# Display_Board.net
KiCad netlist of a schematic drawn in EAGLE
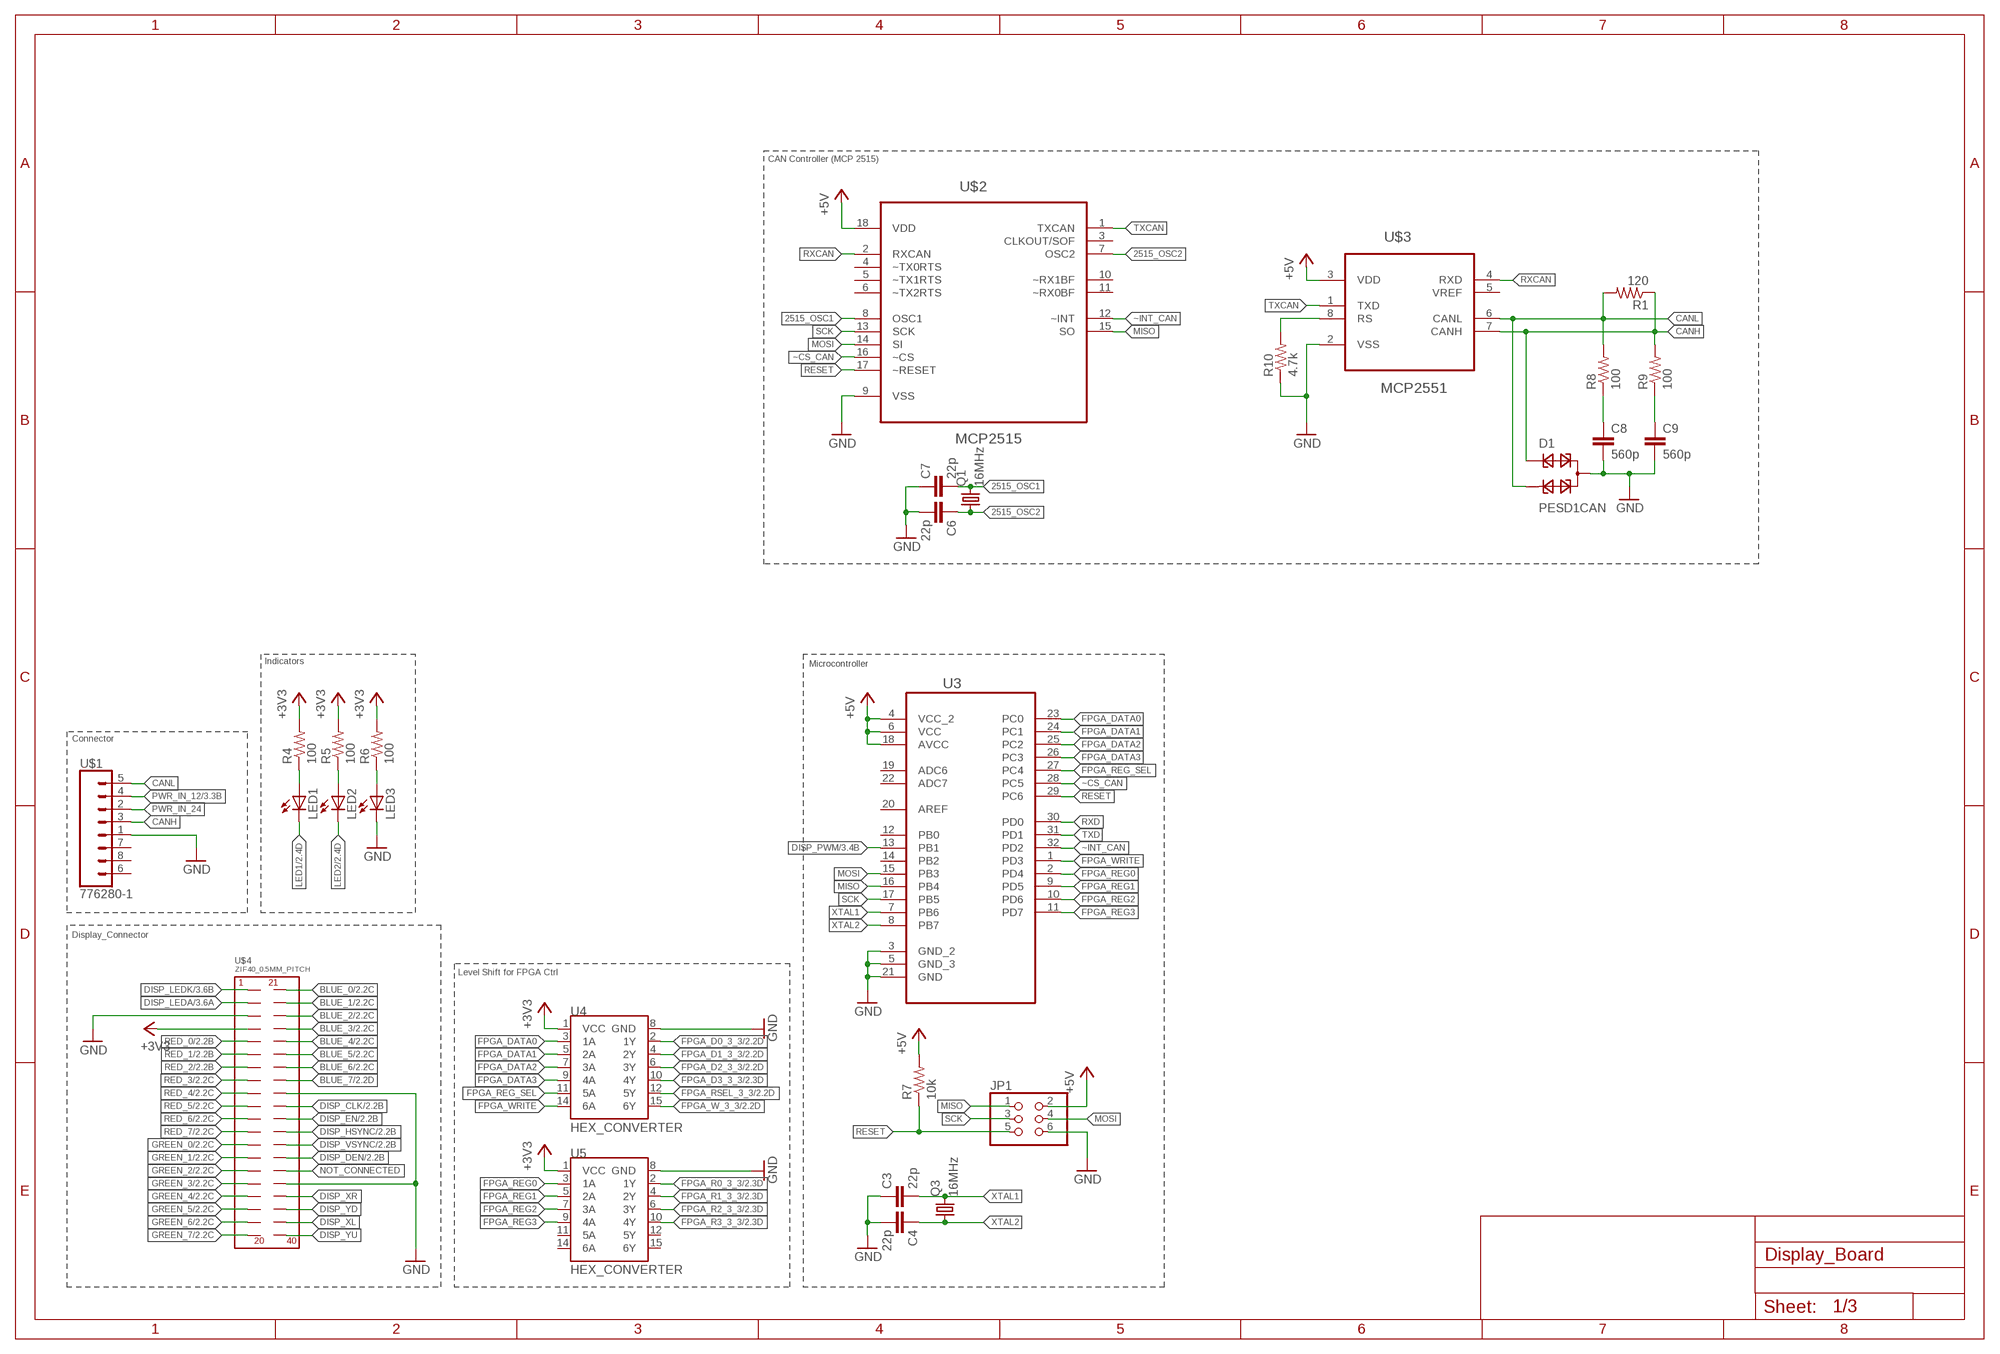
[diagram p0: schematic, sheet 1]
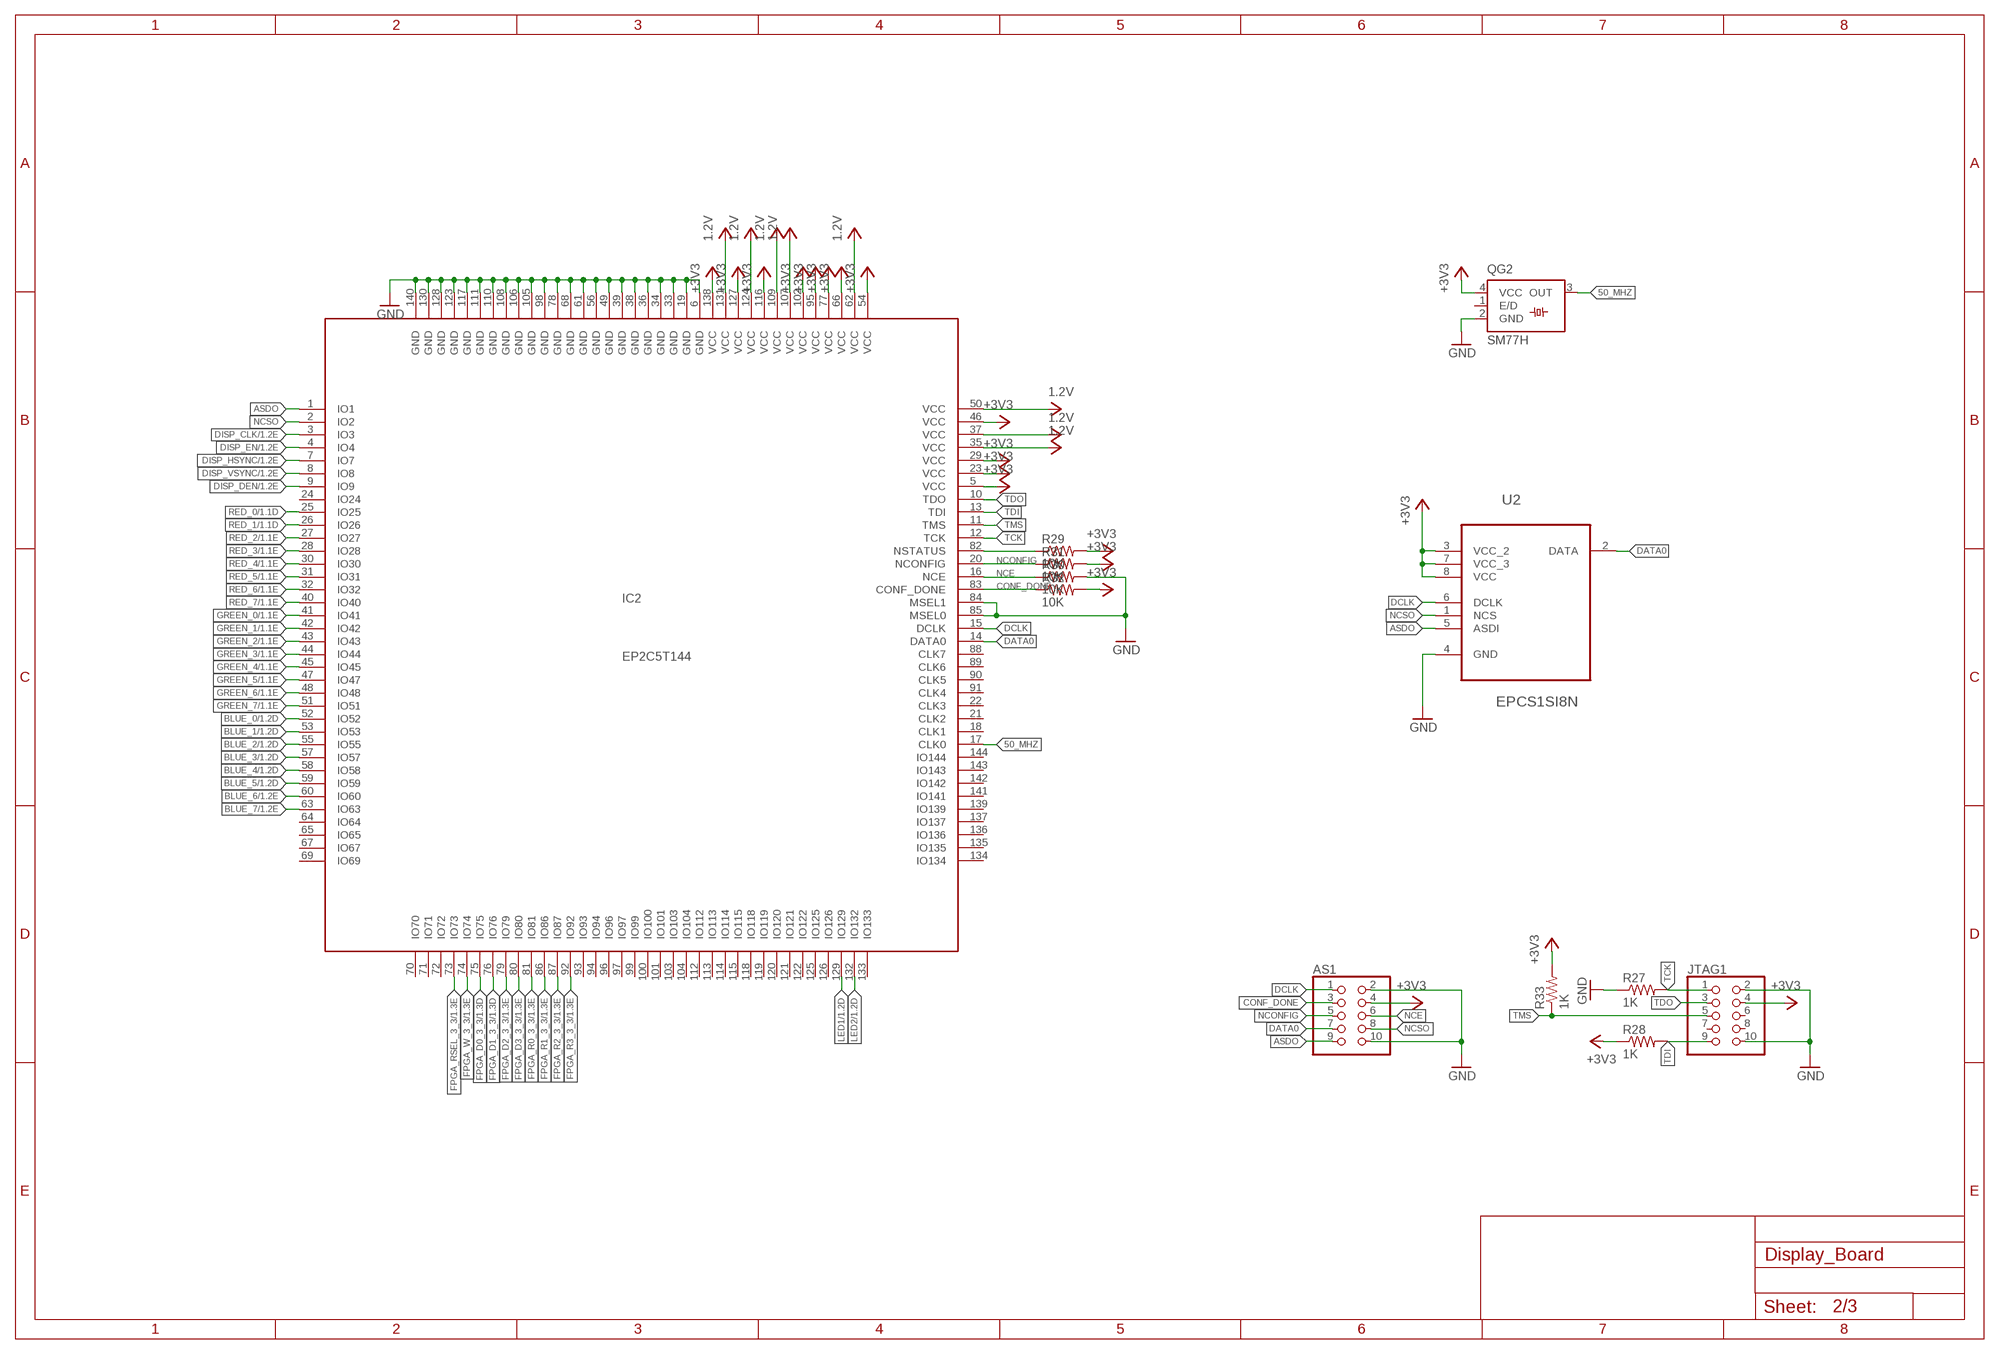
[diagram p1: schematic, sheet 2]
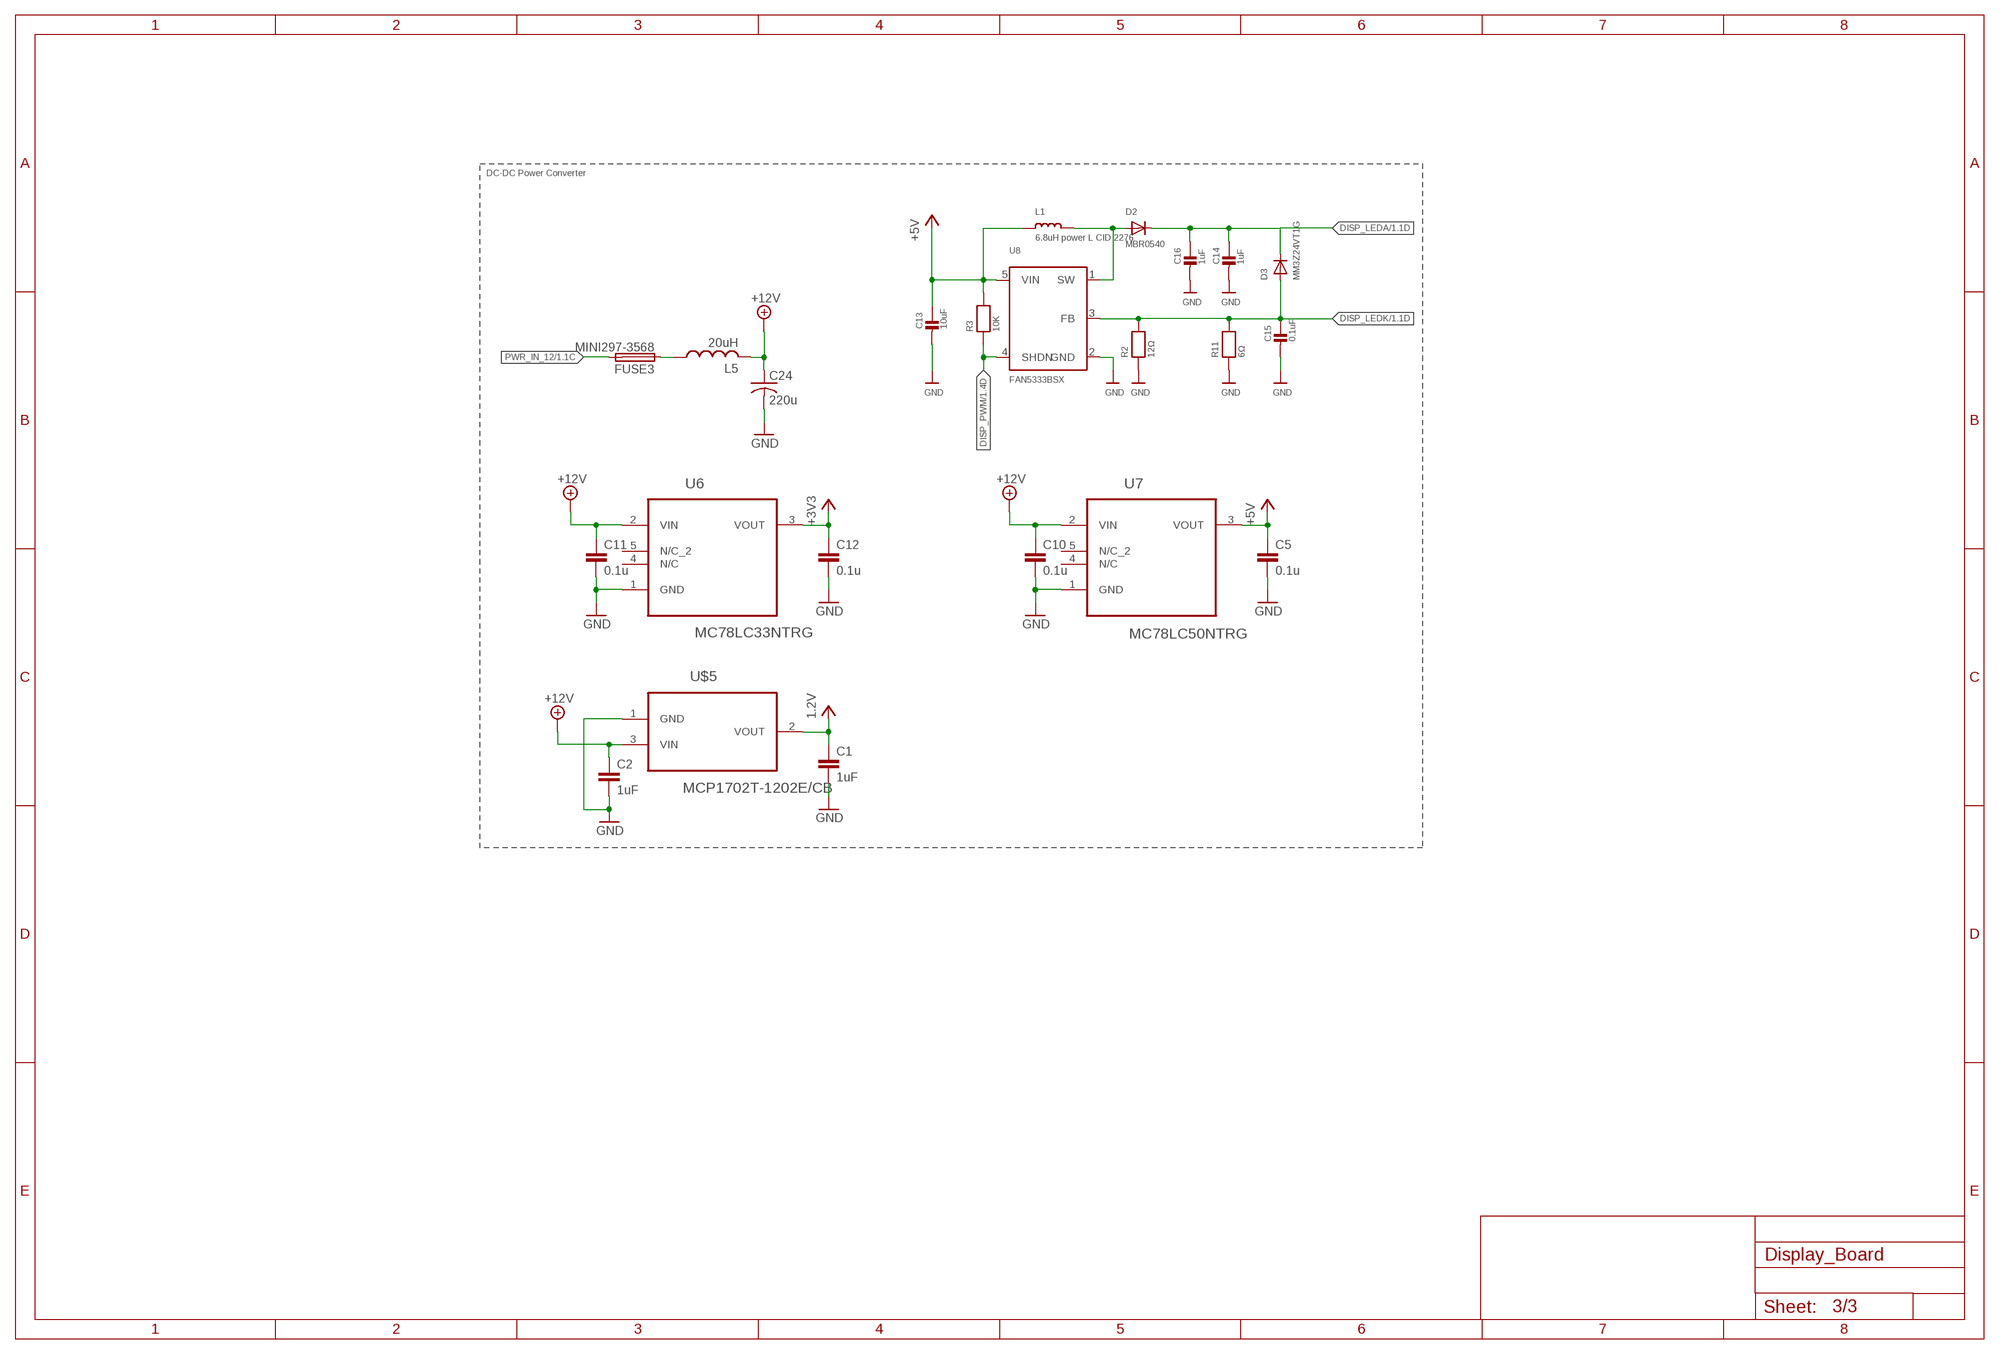
[diagram p2: schematic, sheet 3]

(export (version "E")
  (design (tool "Eeschema 10.0.6"))
  (components
    (comp (ref "AS1")
      (value "PINHD-2X5")
      (footprint "eagle-import:2X05")
      (libsource (lib "eagle-import") (part "PINHD-2X5"))
    )
    (comp (ref "IC2")
      (value "EP2C5T144")
      (footprint "eagle-import:TQFP144")
      (fields (field (name "MPN") "EP2C5T144C8N"))
      (libsource (lib "eagle-import") (part "EP2C5T144"))
    )
    (comp (ref "JTAG1")
      (value "PINHD-2X5")
      (footprint "eagle-import:2X05")
      (libsource (lib "eagle-import") (part "PINHD-2X5"))
    )
    (comp (ref "QG2")
      (value "SM77H")
      (footprint "eagle-import:SM77H")
      (libsource (lib "eagle-import") (part "SM77H"))
    )
    (comp (ref "R27")
      (value "1K")
      (footprint "eagle-import:R0805")
      (libsource (lib "eagle-import") (part "resistor_R-US_R0805"))
    )
    (comp (ref "R28")
      (value "1K")
      (footprint "eagle-import:R0805")
      (libsource (lib "eagle-import") (part "resistor_R-US_R0805"))
    )
    (comp (ref "R29")
      (value "10K")
      (footprint "eagle-import:R0805")
      (libsource (lib "eagle-import") (part "resistor_R-US_R0805"))
    )
    (comp (ref "R30")
      (value "10K")
      (footprint "eagle-import:R0805")
      (libsource (lib "eagle-import") (part "resistor_R-US_R0805"))
    )
    (comp (ref "R31")
      (value "10K")
      (footprint "eagle-import:R0805")
      (libsource (lib "eagle-import") (part "resistor_R-US_R0805"))
    )
    (comp (ref "R32")
      (value "10K")
      (footprint "eagle-import:R0805")
      (libsource (lib "eagle-import") (part "resistor_R-US_R0805"))
    )
    (comp (ref "R33")
      (value "1K")
      (footprint "eagle-import:R0805")
      (libsource (lib "eagle-import") (part "resistor_R-US_R0805"))
    )
    (comp (ref "U2")
      (value "EPCS1SI8N")
      (footprint "eagle-import:SOIC127P600X175-8N")
      (libsource (lib "eagle-import") (part "EPCS1SI8N"))
    )
    (comp (ref "C3")
      (value "22p")
      (footprint "eagle-import:C0805K")
      (libsource (lib "eagle-import") (part "resistor_C-EUC0805K"))
    )
    (comp (ref "C4")
      (value "22p")
      (footprint "eagle-import:C0805K")
      (libsource (lib "eagle-import") (part "resistor_C-EUC0805K"))
    )
    (comp (ref "C6")
      (value "22p")
      (footprint "eagle-import:C0805K")
      (libsource (lib "eagle-import") (part "resistor_C-EUC0805K"))
    )
    (comp (ref "C7")
      (value "22p")
      (footprint "eagle-import:C0805K")
      (libsource (lib "eagle-import") (part "resistor_C-EUC0805K"))
    )
    (comp (ref "C8")
      (value "560p")
      (footprint "eagle-import:C0805K")
      (libsource (lib "eagle-import") (part "C-EUC0805K"))
    )
    (comp (ref "C9")
      (value "560p")
      (footprint "eagle-import:C0805K")
      (libsource (lib "eagle-import") (part "C-EUC0805K"))
    )
    (comp (ref "D1")
      (value "PESD1CAN")
      (footprint "eagle-import:SOT23")
      (libsource (lib "eagle-import") (part "PESD1CAN"))
    )
    (comp (ref "JP1")
      (value "PINHD-2X3")
      (footprint "eagle-import:2X03")
      (libsource (lib "eagle-import") (part "PINHD-2X3"))
    )
    (comp (ref "LED1")
      (value "LEDCHIP-LED0805")
      (footprint "eagle-import:CHIP-LED0805")
      (libsource (lib "eagle-import") (part "LEDCHIP-LED0805"))
    )
    (comp (ref "LED2")
      (value "LEDCHIP-LED0805")
      (footprint "eagle-import:CHIP-LED0805")
      (libsource (lib "eagle-import") (part "LEDCHIP-LED0805"))
    )
    (comp (ref "LED3")
      (value "LEDCHIP-LED0805")
      (footprint "eagle-import:CHIP-LED0805")
      (libsource (lib "eagle-import") (part "LEDCHIP-LED0805"))
    )
    (comp (ref "Q1")
      (value "16MHz")
      (footprint "eagle-import:CTS406")
      (libsource (lib "eagle-import") (part "CRYSTALCTS406"))
    )
    (comp (ref "Q3")
      (value "16MHz")
      (footprint "eagle-import:CTS406")
      (libsource (lib "eagle-import") (part "CRYSTALCTS406"))
    )
    (comp (ref "R1")
      (value "120")
      (footprint "eagle-import:R0805")
      (libsource (lib "eagle-import") (part "R-US_R0805"))
    )
    (comp (ref "R4")
      (value "100")
      (footprint "eagle-import:R0805")
      (libsource (lib "eagle-import") (part "resistor_R-US_R0805"))
    )
    (comp (ref "R5")
      (value "100")
      (footprint "eagle-import:R0805")
      (libsource (lib "eagle-import") (part "resistor_R-US_R0805"))
    )
    (comp (ref "R6")
      (value "100")
      (footprint "eagle-import:R0805")
      (libsource (lib "eagle-import") (part "resistor_R-US_R0805"))
    )
    (comp (ref "R7")
      (value "10k")
      (footprint "eagle-import:R0805")
      (libsource (lib "eagle-import") (part "R-US_R0805"))
    )
    (comp (ref "R8")
      (value "100")
      (footprint "eagle-import:R0805")
      (libsource (lib "eagle-import") (part "R-US_R0805"))
    )
    (comp (ref "R9")
      (value "100")
      (footprint "eagle-import:R0805")
      (libsource (lib "eagle-import") (part "R-US_R0805"))
    )
    (comp (ref "R10")
      (value "4.7k")
      (footprint "eagle-import:R0805")
      (libsource (lib "eagle-import") (part "R-US_R0805"))
    )
    (comp (ref "U$1")
      (value "776280-1")
      (footprint "eagle-import:776280-1")
      (libsource (lib "eagle-import") (part "776280-1"))
    )
    (comp (ref "U$2")
      (value "MCP2515")
      (footprint "eagle-import:SOIC127P1034X264-18N")
      (fields (field (name "MPN") "MCP2515-I/SO"))
      (libsource (lib "eagle-import") (part "MCP2515-I/SO"))
    )
    (comp (ref "U$3")
      (value "MCP2551")
      (footprint "eagle-import:SOIC127P600X175-8N")
      (fields (field (name "MPN") "MCP2551-I/SN"))
      (libsource (lib "eagle-import") (part "MCP2551-I/SN"))
    )
    (comp (ref "U$4")
      (value "ZIF40_0.5MM_PITCH")
      (footprint "eagle-import:ZIF40")
      (libsource (lib "eagle-import") (part "ZIF40_0.5MM_PITCH"))
    )
    (comp (ref "U3")
      (value "ATMEGA328P-AU")
      (footprint "eagle-import:QFP80P900X900X120-32N")
      (libsource (lib "eagle-import") (part "ATMEGA328P-AU"))
    )
    (comp (ref "U4")
      (value "HEX_CONVERTER")
      (footprint "eagle-import:SO016")
      (libsource (lib "eagle-import") (part "HEX_CONVERTER"))
    )
    (comp (ref "U5")
      (value "HEX_CONVERTER")
      (footprint "eagle-import:SO016")
      (libsource (lib "eagle-import") (part "HEX_CONVERTER"))
    )
    (comp (ref "C1")
      (value "1uF")
      (footprint "eagle-import:C0805K")
      (libsource (lib "eagle-import") (part "C-EUC0805K"))
    )
    (comp (ref "C2")
      (value "1uF")
      (footprint "eagle-import:C0805K")
      (libsource (lib "eagle-import") (part "C-EUC0805K"))
    )
    (comp (ref "C5")
      (value "0.1u")
      (footprint "eagle-import:C0805K")
      (libsource (lib "eagle-import") (part "C-EUC0805K"))
    )
    (comp (ref "C10")
      (value "0.1u")
      (footprint "eagle-import:C0805K")
      (libsource (lib "eagle-import") (part "C-EUC0805K"))
    )
    (comp (ref "C11")
      (value "0.1u")
      (footprint "eagle-import:C0805K")
      (libsource (lib "eagle-import") (part "C-EUC0805K"))
    )
    (comp (ref "C12")
      (value "0.1u")
      (footprint "eagle-import:C0805K")
      (libsource (lib "eagle-import") (part "C-EUC0805K"))
    )
    (comp (ref "C13")
      (value "10uF")
      (footprint "eagle-import:_0805MP")
      (libsource (lib "eagle-import") (part "CAP_CERAMIC_0805MP"))
    )
    (comp (ref "C14")
      (value "1uF")
      (footprint "eagle-import:_0805MP")
      (libsource (lib "eagle-import") (part "CAP_CERAMIC_0805MP"))
    )
    (comp (ref "C15")
      (value "0.1uF")
      (footprint "eagle-import:_0805MP")
      (libsource (lib "eagle-import") (part "CAP_CERAMIC_0805MP"))
    )
    (comp (ref "C16")
      (value "1uF")
      (footprint "eagle-import:_0805MP")
      (libsource (lib "eagle-import") (part "CAP_CERAMIC_0805MP"))
    )
    (comp (ref "C24")
      (value "220u")
      (footprint "eagle-import:C1206")
      (libsource (lib "eagle-import") (part "C1206"))
    )
    (comp (ref "D2")
      (value "MBR0540")
      (footprint "eagle-import:SOD-123")
      (libsource (lib "eagle-import") (part "DIODESOD-123"))
    )
    (comp (ref "D3")
      (value "MM3Z24VT1G")
      (footprint "eagle-import:SMADIODE")
      (libsource (lib "eagle-import") (part "DIODESMA"))
    )
    (comp (ref "FUSE3")
      (value "MINI297-3568")
      (footprint "eagle-import:3568")
      (libsource (lib "eagle-import") (part "MINI297-3568"))
    )
    (comp (ref "L1")
      (value "6.8uH power L CID 2276")
      (footprint "eagle-import:INDUCTOR_5X5MM_NR5040_NOTHERMALS")
      (libsource (lib "eagle-import") (part "INDUCTORNR5040"))
    )
    (comp (ref "L5")
      (value "20uH")
      (footprint "eagle-import:MSS7348")
      (libsource (lib "eagle-import") (part "MSS7348"))
    )
    (comp (ref "R2")
      (value "12Ω")
      (footprint "eagle-import:_0805MP")
      (libsource (lib "eagle-import") (part "RESISTOR_0805MP"))
    )
    (comp (ref "R3")
      (value "10K")
      (footprint "eagle-import:_0805MP")
      (libsource (lib "eagle-import") (part "RESISTOR_0805MP"))
    )
    (comp (ref "R11")
      (value "6Ω")
      (footprint "eagle-import:_0805MP")
      (libsource (lib "eagle-import") (part "RESISTOR_0805MP"))
    )
    (comp (ref "U$5")
      (value "MCP1702T-1202E/CB")
      (footprint "eagle-import:SOT95P300X145-3N")
      (fields (field (name "MPN") "MCP1702T-1802E/CB"))
      (libsource (lib "eagle-import") (part "MCP1702T-1802E/CB"))
    )
    (comp (ref "U6")
      (value "MC78LC33NTRG")
      (footprint "eagle-import:SOT95P275X110-5N")
      (libsource (lib "eagle-import") (part "MC78LC33NTRG"))
    )
    (comp (ref "U7")
      (value "MC78LC50NTRG")
      (footprint "eagle-import:SOT95P275X110-5N")
      (libsource (lib "eagle-import") (part "MC78LC50NTRG"))
    )
    (comp (ref "U8")
      (value "FAN5333BSX")
      (footprint "eagle-import:SOT23-5@1")
      (libsource (lib "eagle-import") (part "FAN5331"))
    )
  )
  (nets
    (net (code "1") (name "+3V3") (class "Default")
      (node (ref "AS1") (pin "4") (pinfunction "4_4") (pintype "passive"))
      (node (ref "C12") (pin "1") (pinfunction "1_1") (pintype "passive"))
      (node (ref "IC2") (pin "102") (pinfunction "VCC_102") (pintype "power_in"))
      (node (ref "IC2") (pin "116") (pinfunction "VCC_116") (pintype "power_in"))
      (node (ref "IC2") (pin "127") (pinfunction "VCC_127") (pintype "power_in"))
      (node (ref "IC2") (pin "138") (pinfunction "VCC_138") (pintype "power_in"))
      (node (ref "IC2") (pin "23") (pinfunction "VCC_23") (pintype "power_in"))
      (node (ref "IC2") (pin "29") (pinfunction "VCC_29") (pintype "power_in"))
      (node (ref "IC2") (pin "46") (pinfunction "VCC_46") (pintype "power_in"))
      (node (ref "IC2") (pin "5") (pinfunction "VCC_5") (pintype "power_in"))
      (node (ref "IC2") (pin "54") (pinfunction "VCC_54") (pintype "power_in"))
      (node (ref "IC2") (pin "66") (pinfunction "VCC_66") (pintype "power_in"))
      (node (ref "IC2") (pin "77") (pinfunction "VCC_77") (pintype "power_in"))
      (node (ref "IC2") (pin "95") (pinfunction "VCC_95") (pintype "power_in"))
      (node (ref "JTAG1") (pin "4") (pinfunction "4_4") (pintype "passive"))
      (node (ref "QG2") (pin "4") (pinfunction "VCC_4") (pintype "power_in"))
      (node (ref "R28") (pin "1") (pinfunction "1_1") (pintype "passive"))
      (node (ref "R29") (pin "2") (pinfunction "2_2") (pintype "passive"))
      (node (ref "R31") (pin "2") (pinfunction "2_2") (pintype "passive"))
      (node (ref "R32") (pin "2") (pinfunction "2_2") (pintype "passive"))
      (node (ref "R33") (pin "2") (pinfunction "2_2") (pintype "passive"))
      (node (ref "R4") (pin "2") (pinfunction "2_2") (pintype "passive"))
      (node (ref "R5") (pin "2") (pinfunction "2_2") (pintype "passive"))
      (node (ref "R6") (pin "2") (pinfunction "2_2") (pintype "passive"))
      (node (ref "U$4") (pin "P$4") (pinfunction "P$4_P$4") (pintype "bidirectional"))
      (node (ref "U2") (pin "3") (pinfunction "VCC_2_3") (pintype "power_in"))
      (node (ref "U2") (pin "7") (pinfunction "VCC_3_7") (pintype "power_in"))
      (node (ref "U2") (pin "8") (pinfunction "VCC_8") (pintype "power_in"))
      (node (ref "U4") (pin "1") (pinfunction "VCC_1") (pintype "bidirectional"))
      (node (ref "U5") (pin "1") (pinfunction "VCC_1") (pintype "bidirectional"))
      (node (ref "U6") (pin "3") (pinfunction "VOUT_3") (pintype "output"))
    )
    (net (code "2") (name "+5V") (class "Default")
      (node (ref "C13") (pin "1") (pinfunction "1_1") (pintype "passive"))
      (node (ref "C5") (pin "1") (pinfunction "1_1") (pintype "passive"))
      (node (ref "JP1") (pin "2") (pinfunction "2_2") (pintype "passive"))
      (node (ref "L1") (pin "P$1") (pinfunction "1_P$1") (pintype "passive"))
      (node (ref "R3") (pin "2") (pinfunction "2_2") (pintype "passive"))
      (node (ref "R7") (pin "2") (pinfunction "2_2") (pintype "passive"))
      (node (ref "U$2") (pin "18") (pinfunction "VDD_18") (pintype "power_in"))
      (node (ref "U$3") (pin "3") (pinfunction "VDD_3") (pintype "power_in"))
      (node (ref "U3") (pin "18") (pinfunction "AVCC_18") (pintype "power_in"))
      (node (ref "U3") (pin "4") (pinfunction "VCC_2_4") (pintype "power_in"))
      (node (ref "U3") (pin "6") (pinfunction "VCC_6") (pintype "power_in"))
      (node (ref "U7") (pin "3") (pinfunction "VOUT_3") (pintype "output"))
      (node (ref "U8") (pin "5") (pinfunction "VIN_5") (pintype "bidirectional"))
    )
    (net (code "3") (name "+12V") (class "Default")
      (node (ref "C10") (pin "1") (pinfunction "1_1") (pintype "passive"))
      (node (ref "C11") (pin "1") (pinfunction "1_1") (pintype "passive"))
      (node (ref "C2") (pin "1") (pinfunction "1_1") (pintype "passive"))
      (node (ref "C24") (pin "1") (pinfunction "1_1") (pintype "passive"))
      (node (ref "L5") (pin "P$2") (pinfunction "2_P$2") (pintype "passive"))
      (node (ref "U$5") (pin "3") (pinfunction "VIN_3") (pintype "power_in"))
      (node (ref "U6") (pin "2") (pinfunction "VIN_2") (pintype "power_in"))
      (node (ref "U7") (pin "2") (pinfunction "VIN_2") (pintype "power_in"))
    )
    (net (code "4") (name "50_MHZ") (class "Default")
      (node (ref "IC2") (pin "17") (pinfunction "CLK0_17") (pintype "bidirectional"))
      (node (ref "QG2") (pin "3") (pinfunction "OUT_3") (pintype "output"))
    )
    (net (code "5") (name "2515_OSC1") (class "Default")
      (node (ref "C7") (pin "2") (pinfunction "2_2") (pintype "passive"))
      (node (ref "Q1") (pin "3") (pinfunction "2_3") (pintype "passive"))
      (node (ref "U$2") (pin "8") (pinfunction "OSC1_8") (pintype "input"))
    )
    (net (code "6") (name "2515_OSC2") (class "Default")
      (node (ref "C6") (pin "1") (pinfunction "1_1") (pintype "passive"))
      (node (ref "Q1") (pin "1") (pinfunction "1_1") (pintype "passive"))
      (node (ref "U$2") (pin "7") (pinfunction "OSC2_7") (pintype "output"))
    )
    (net (code "7") (name "ASDO") (class "Default")
      (node (ref "AS1") (pin "9") (pinfunction "9_9") (pintype "passive"))
      (node (ref "IC2") (pin "1") (pinfunction "IO1_1") (pintype "output"))
      (node (ref "U2") (pin "5") (pinfunction "ASDI_5") (pintype "input"))
    )
    (net (code "8") (name "BLUE_0") (class "Default")
      (node (ref "IC2") (pin "52") (pinfunction "IO52_52") (pintype "bidirectional"))
      (node (ref "U$4") (pin "P$21") (pinfunction "P$21_P$21") (pintype "bidirectional"))
    )
    (net (code "9") (name "BLUE_1") (class "Default")
      (node (ref "IC2") (pin "53") (pinfunction "IO53_53") (pintype "bidirectional"))
      (node (ref "U$4") (pin "P$22") (pinfunction "P$22_P$22") (pintype "bidirectional"))
    )
    (net (code "10") (name "BLUE_2") (class "Default")
      (node (ref "IC2") (pin "55") (pinfunction "IO55_55") (pintype "bidirectional"))
      (node (ref "U$4") (pin "P$23") (pinfunction "P$23_P$23") (pintype "bidirectional"))
    )
    (net (code "11") (name "BLUE_3") (class "Default")
      (node (ref "IC2") (pin "57") (pinfunction "IO57_57") (pintype "bidirectional"))
      (node (ref "U$4") (pin "P$24") (pinfunction "P$24_P$24") (pintype "bidirectional"))
    )
    (net (code "12") (name "BLUE_4") (class "Default")
      (node (ref "IC2") (pin "58") (pinfunction "IO58_58") (pintype "bidirectional"))
      (node (ref "U$4") (pin "P$25") (pinfunction "P$25_P$25") (pintype "bidirectional"))
    )
    (net (code "13") (name "BLUE_5") (class "Default")
      (node (ref "IC2") (pin "59") (pinfunction "IO59_59") (pintype "bidirectional"))
      (node (ref "U$4") (pin "P$26") (pinfunction "P$26_P$26") (pintype "bidirectional"))
    )
    (net (code "14") (name "BLUE_6") (class "Default")
      (node (ref "IC2") (pin "60") (pinfunction "IO60_60") (pintype "bidirectional"))
      (node (ref "U$4") (pin "P$27") (pinfunction "P$27_P$27") (pintype "bidirectional"))
    )
    (net (code "15") (name "BLUE_7") (class "Default")
      (node (ref "IC2") (pin "63") (pinfunction "IO63_63") (pintype "bidirectional"))
      (node (ref "U$4") (pin "P$28") (pinfunction "P$28_P$28") (pintype "bidirectional"))
    )
    (net (code "16") (name "CANH") (class "Default")
      (node (ref "D1") (pin "1") (pinfunction "1_1") (pintype "passive"))
      (node (ref "R1") (pin "1") (pinfunction "1_1") (pintype "passive"))
      (node (ref "R9") (pin "2") (pinfunction "2_2") (pintype "passive"))
      (node (ref "U$1") (pin "3") (pinfunction "5_3") (pintype "passive"))
      (node (ref "U$3") (pin "7") (pinfunction "CANH_7") (pintype "bidirectional"))
    )
    (net (code "17") (name "CANL") (class "Default")
      (node (ref "D1") (pin "2") (pinfunction "2_2") (pintype "passive"))
      (node (ref "R1") (pin "2") (pinfunction "2_2") (pintype "passive"))
      (node (ref "R8") (pin "2") (pinfunction "2_2") (pintype "passive"))
      (node (ref "U$1") (pin "5") (pinfunction "8_5") (pintype "passive"))
      (node (ref "U$3") (pin "6") (pinfunction "CANL_6") (pintype "bidirectional"))
    )
    (net (code "18") (name "CONF_DONE") (class "Default")
      (node (ref "AS1") (pin "3") (pinfunction "3_3") (pintype "passive"))
      (node (ref "IC2") (pin "83") (pinfunction "CONF_DONE_83") (pintype "input"))
      (node (ref "R32") (pin "1") (pinfunction "1_1") (pintype "passive"))
    )
    (net (code "19") (name "DATA0") (class "Default")
      (node (ref "AS1") (pin "7") (pinfunction "7_7") (pintype "passive"))
      (node (ref "IC2") (pin "14") (pinfunction "DATA0_14") (pintype "bidirectional"))
      (node (ref "U2") (pin "2") (pinfunction "DATA_2") (pintype "output"))
    )
    (net (code "20") (name "DCLK") (class "Default")
      (node (ref "AS1") (pin "1") (pinfunction "1_1") (pintype "passive"))
      (node (ref "IC2") (pin "15") (pinfunction "DCLK_15") (pintype "bidirectional"))
      (node (ref "U2") (pin "6") (pinfunction "DCLK_6") (pintype "input"))
    )
    (net (code "21") (name "DISP_CLK") (class "Default")
      (node (ref "IC2") (pin "3") (pinfunction "IO3_3") (pintype "bidirectional"))
      (node (ref "U$4") (pin "P$30") (pinfunction "P$30_P$30") (pintype "bidirectional"))
    )
    (net (code "22") (name "DISP_DEN") (class "Default")
      (node (ref "IC2") (pin "9") (pinfunction "IO9_9") (pintype "bidirectional"))
      (node (ref "U$4") (pin "P$34") (pinfunction "P$34_P$34") (pintype "bidirectional"))
    )
    (net (code "23") (name "DISP_EN") (class "Default")
      (node (ref "IC2") (pin "4") (pinfunction "IO4_4") (pintype "bidirectional"))
      (node (ref "U$4") (pin "P$31") (pinfunction "P$31_P$31") (pintype "bidirectional"))
    )
    (net (code "24") (name "DISP_HSYNC") (class "Default")
      (node (ref "IC2") (pin "7") (pinfunction "IO7_7") (pintype "bidirectional"))
      (node (ref "U$4") (pin "P$32") (pinfunction "P$32_P$32") (pintype "bidirectional"))
    )
    (net (code "25") (name "DISP_LEDA") (class "Default")
      (node (ref "C14") (pin "1") (pinfunction "1_1") (pintype "passive"))
      (node (ref "C16") (pin "1") (pinfunction "1_1") (pintype "passive"))
      (node (ref "D2") (pin "C") (pinfunction "C_C") (pintype "passive"))
      (node (ref "D3") (pin "C") (pinfunction "C_C") (pintype "passive"))
      (node (ref "U$4") (pin "P$2") (pinfunction "P$2_P$2") (pintype "bidirectional"))
    )
    (net (code "26") (name "DISP_LEDK") (class "Default")
      (node (ref "C15") (pin "1") (pinfunction "1_1") (pintype "passive"))
      (node (ref "D3") (pin "A") (pinfunction "A_A") (pintype "passive"))
      (node (ref "R11") (pin "2") (pinfunction "2_2") (pintype "passive"))
      (node (ref "R2") (pin "2") (pinfunction "2_2") (pintype "passive"))
      (node (ref "U$4") (pin "P$1") (pinfunction "P$1_P$1") (pintype "bidirectional"))
      (node (ref "U8") (pin "3") (pinfunction "FB_3") (pintype "bidirectional"))
    )
    (net (code "27") (name "DISP_PWM") (class "Default")
      (node (ref "R3") (pin "1") (pinfunction "1_1") (pintype "passive"))
      (node (ref "U3") (pin "13") (pinfunction "PB1_13") (pintype "bidirectional"))
      (node (ref "U8") (pin "4") (pinfunction "SHDN_4") (pintype "bidirectional"))
    )
    (net (code "28") (name "DISP_VSYNC") (class "Default")
      (node (ref "IC2") (pin "8") (pinfunction "IO8_8") (pintype "bidirectional"))
      (node (ref "U$4") (pin "P$33") (pinfunction "P$33_P$33") (pintype "bidirectional"))
    )
    (net (code "29") (name "DISP_XL") (class "Default")
      (node (ref "U$4") (pin "P$39") (pinfunction "P$39_P$39") (pintype "bidirectional"))
    )
    (net (code "30") (name "DISP_XR") (class "Default")
      (node (ref "U$4") (pin "P$37") (pinfunction "P$37_P$37") (pintype "bidirectional"))
    )
    (net (code "31") (name "DISP_YD") (class "Default")
      (node (ref "U$4") (pin "P$38") (pinfunction "P$38_P$38") (pintype "bidirectional"))
    )
    (net (code "32") (name "DISP_YU") (class "Default")
      (node (ref "U$4") (pin "P$40") (pinfunction "P$40_P$40") (pintype "bidirectional"))
    )
    (net (code "33") (name "FPGA_D0_3_3") (class "Default")
      (node (ref "IC2") (pin "75") (pinfunction "IO75_75") (pintype "bidirectional"))
      (node (ref "U4") (pin "2") (pinfunction "1Y_2") (pintype "bidirectional"))
    )
    (net (code "34") (name "FPGA_D1_3_3") (class "Default")
      (node (ref "IC2") (pin "76") (pinfunction "IO76_76") (pintype "bidirectional"))
      (node (ref "U4") (pin "4") (pinfunction "2Y_4") (pintype "bidirectional"))
    )
    (net (code "35") (name "FPGA_D2_3_3") (class "Default")
      (node (ref "IC2") (pin "79") (pinfunction "IO79_79") (pintype "bidirectional"))
      (node (ref "U4") (pin "6") (pinfunction "3Y_6") (pintype "bidirectional"))
    )
    (net (code "36") (name "FPGA_D3_3_3") (class "Default")
      (node (ref "IC2") (pin "80") (pinfunction "IO80_80") (pintype "bidirectional"))
      (node (ref "U4") (pin "10") (pinfunction "4Y_10") (pintype "bidirectional"))
    )
    (net (code "37") (name "FPGA_DATA0") (class "Default")
      (node (ref "U3") (pin "23") (pinfunction "PC0_23") (pintype "bidirectional"))
      (node (ref "U4") (pin "3") (pinfunction "1A_3") (pintype "bidirectional"))
    )
    (net (code "38") (name "FPGA_DATA1") (class "Default")
      (node (ref "U3") (pin "24") (pinfunction "PC1_24") (pintype "bidirectional"))
      (node (ref "U4") (pin "5") (pinfunction "2A_5") (pintype "bidirectional"))
    )
    (net (code "39") (name "FPGA_DATA2") (class "Default")
      (node (ref "U3") (pin "25") (pinfunction "PC2_25") (pintype "bidirectional"))
      (node (ref "U4") (pin "7") (pinfunction "3A_7") (pintype "bidirectional"))
    )
    (net (code "40") (name "FPGA_DATA3") (class "Default")
      (node (ref "U3") (pin "26") (pinfunction "PC3_26") (pintype "bidirectional"))
      (node (ref "U4") (pin "9") (pinfunction "4A_9") (pintype "bidirectional"))
    )
    (net (code "41") (name "FPGA_R0_3_3") (class "Default")
      (node (ref "IC2") (pin "81") (pinfunction "IO81_81") (pintype "bidirectional"))
      (node (ref "U5") (pin "2") (pinfunction "1Y_2") (pintype "bidirectional"))
    )
    (net (code "42") (name "FPGA_R1_3_3") (class "Default")
      (node (ref "IC2") (pin "86") (pinfunction "IO86_86") (pintype "bidirectional"))
      (node (ref "U5") (pin "4") (pinfunction "2Y_4") (pintype "bidirectional"))
    )
    (net (code "43") (name "FPGA_R2_3_3") (class "Default")
      (node (ref "IC2") (pin "87") (pinfunction "IO87_87") (pintype "bidirectional"))
      (node (ref "U5") (pin "6") (pinfunction "3Y_6") (pintype "bidirectional"))
    )
    (net (code "44") (name "FPGA_R3_3_3") (class "Default")
      (node (ref "IC2") (pin "92") (pinfunction "IO92_92") (pintype "bidirectional"))
      (node (ref "U5") (pin "10") (pinfunction "4Y_10") (pintype "bidirectional"))
    )
    (net (code "45") (name "FPGA_REG0") (class "Default")
      (node (ref "U3") (pin "2") (pinfunction "PD4_2") (pintype "bidirectional"))
      (node (ref "U5") (pin "3") (pinfunction "1A_3") (pintype "bidirectional"))
    )
    (net (code "46") (name "FPGA_REG1") (class "Default")
      (node (ref "U3") (pin "9") (pinfunction "PD5_9") (pintype "bidirectional"))
      (node (ref "U5") (pin "5") (pinfunction "2A_5") (pintype "bidirectional"))
    )
    (net (code "47") (name "FPGA_REG2") (class "Default")
      (node (ref "U3") (pin "10") (pinfunction "PD6_10") (pintype "bidirectional"))
      (node (ref "U5") (pin "7") (pinfunction "3A_7") (pintype "bidirectional"))
    )
    (net (code "48") (name "FPGA_REG3") (class "Default")
      (node (ref "U3") (pin "11") (pinfunction "PD7_11") (pintype "bidirectional"))
      (node (ref "U5") (pin "9") (pinfunction "4A_9") (pintype "bidirectional"))
    )
    (net (code "49") (name "FPGA_REG_SEL") (class "Default")
      (node (ref "U3") (pin "27") (pinfunction "PC4_27") (pintype "bidirectional"))
      (node (ref "U4") (pin "11") (pinfunction "5A_11") (pintype "bidirectional"))
    )
    (net (code "50") (name "FPGA_RSEL_3_3") (class "Default")
      (node (ref "IC2") (pin "73") (pinfunction "IO73_73") (pintype "bidirectional"))
      (node (ref "U4") (pin "12") (pinfunction "5Y_12") (pintype "bidirectional"))
    )
    (net (code "51") (name "FPGA_WRITE") (class "Default")
      (node (ref "U3") (pin "1") (pinfunction "PD3_1") (pintype "bidirectional"))
      (node (ref "U4") (pin "14") (pinfunction "6A_14") (pintype "bidirectional"))
    )
    (net (code "52") (name "FPGA_W_3_3") (class "Default")
      (node (ref "IC2") (pin "74") (pinfunction "IO74_74") (pintype "bidirectional"))
      (node (ref "U4") (pin "15") (pinfunction "6Y_15") (pintype "bidirectional"))
    )
    (net (code "53") (name "GND") (class "Default")
      (node (ref "AS1") (pin "10") (pinfunction "10_10") (pintype "passive"))
      (node (ref "AS1") (pin "2") (pinfunction "2_2") (pintype "passive"))
      (node (ref "C1") (pin "2") (pinfunction "2_2") (pintype "passive"))
      (node (ref "C10") (pin "2") (pinfunction "2_2") (pintype "passive"))
      (node (ref "C11") (pin "2") (pinfunction "2_2") (pintype "passive"))
      (node (ref "C12") (pin "2") (pinfunction "2_2") (pintype "passive"))
      (node (ref "C13") (pin "2") (pinfunction "2_2") (pintype "passive"))
      (node (ref "C14") (pin "2") (pinfunction "2_2") (pintype "passive"))
      (node (ref "C15") (pin "2") (pinfunction "2_2") (pintype "passive"))
      (node (ref "C16") (pin "2") (pinfunction "2_2") (pintype "passive"))
      (node (ref "C2") (pin "2") (pinfunction "2_2") (pintype "passive"))
      (node (ref "C24") (pin "2") (pinfunction "2_2") (pintype "passive"))
      (node (ref "C3") (pin "1") (pinfunction "1_1") (pintype "passive"))
      (node (ref "C4") (pin "2") (pinfunction "2_2") (pintype "passive"))
      (node (ref "C5") (pin "2") (pinfunction "2_2") (pintype "passive"))
      (node (ref "C6") (pin "2") (pinfunction "2_2") (pintype "passive"))
      (node (ref "C7") (pin "1") (pinfunction "1_1") (pintype "passive"))
      (node (ref "C8") (pin "2") (pinfunction "2_2") (pintype "passive"))
      (node (ref "C9") (pin "2") (pinfunction "2_2") (pintype "passive"))
      (node (ref "D1") (pin "3") (pinfunction "3_3") (pintype "passive"))
      (node (ref "IC2") (pin "105") (pinfunction "GND_105") (pintype "power_in"))
      (node (ref "IC2") (pin "106") (pinfunction "GND_106") (pintype "power_in"))
      (node (ref "IC2") (pin "108") (pinfunction "GND_108") (pintype "power_in"))
      (node (ref "IC2") (pin "110") (pinfunction "GND_110") (pintype "power_in"))
      (node (ref "IC2") (pin "111") (pinfunction "GND_111") (pintype "power_in"))
      (node (ref "IC2") (pin "117") (pinfunction "GND_117") (pintype "power_in"))
      (node (ref "IC2") (pin "123") (pinfunction "GND_123") (pintype "power_in"))
      (node (ref "IC2") (pin "128") (pinfunction "GND_128") (pintype "power_in"))
      (node (ref "IC2") (pin "130") (pinfunction "GND_130") (pintype "power_in"))
      (node (ref "IC2") (pin "140") (pinfunction "GND_140") (pintype "power_in"))
      (node (ref "IC2") (pin "19") (pinfunction "GND_19") (pintype "power_in"))
      (node (ref "IC2") (pin "33") (pinfunction "GND_33") (pintype "power_in"))
      (node (ref "IC2") (pin "34") (pinfunction "GND_34") (pintype "power_in"))
      (node (ref "IC2") (pin "36") (pinfunction "GND_36") (pintype "power_in"))
      (node (ref "IC2") (pin "38") (pinfunction "GND_38") (pintype "power_in"))
      (node (ref "IC2") (pin "39") (pinfunction "GND_39") (pintype "power_in"))
      (node (ref "IC2") (pin "49") (pinfunction "GND_49") (pintype "power_in"))
      (node (ref "IC2") (pin "56") (pinfunction "GND_56") (pintype "power_in"))
      (node (ref "IC2") (pin "6") (pinfunction "GND_6") (pintype "power_in"))
      (node (ref "IC2") (pin "61") (pinfunction "GND_61") (pintype "power_in"))
      (node (ref "IC2") (pin "68") (pinfunction "GND_68") (pintype "power_in"))
      (node (ref "IC2") (pin "78") (pinfunction "GND_78") (pintype "power_in"))
      (node (ref "IC2") (pin "84") (pinfunction "MSEL1_84") (pintype "input"))
      (node (ref "IC2") (pin "85") (pinfunction "MSEL0_85") (pintype "input"))
      (node (ref "IC2") (pin "98") (pinfunction "GND_98") (pintype "power_in"))
      (node (ref "JP1") (pin "6") (pinfunction "6_6") (pintype "passive"))
      (node (ref "JTAG1") (pin "10") (pinfunction "10_10") (pintype "passive"))
      (node (ref "JTAG1") (pin "2") (pinfunction "2_2") (pintype "passive"))
      (node (ref "LED3") (pin "C") (pinfunction "C_C") (pintype "passive"))
      (node (ref "QG2") (pin "2") (pinfunction "GND_2") (pintype "power_in"))
      (node (ref "R10") (pin "1") (pinfunction "1_1") (pintype "passive"))
      (node (ref "R11") (pin "1") (pinfunction "1_1") (pintype "passive"))
      (node (ref "R2") (pin "1") (pinfunction "1_1") (pintype "passive"))
      (node (ref "R27") (pin "1") (pinfunction "1_1") (pintype "passive"))
      (node (ref "R30") (pin "2") (pinfunction "2_2") (pintype "passive"))
      (node (ref "U$1") (pin "1") (pinfunction "4_1") (pintype "passive"))
      (node (ref "U$2") (pin "9") (pinfunction "VSS_9") (pintype "power_in"))
      (node (ref "U$3") (pin "2") (pinfunction "VSS_2") (pintype "passive"))
      (node (ref "U$4") (pin "P$29") (pinfunction "P$29_P$29") (pintype "bidirectional"))
      (node (ref "U$4") (pin "P$3") (pinfunction "P$3_P$3") (pintype "bidirectional"))
      (node (ref "U$4") (pin "P$36") (pinfunction "P$36_P$36") (pintype "bidirectional"))
      (node (ref "U$5") (pin "1") (pinfunction "GND_1") (pintype "passive"))
      (node (ref "U2") (pin "4") (pinfunction "GND_4") (pintype "passive"))
      (node (ref "U3") (pin "21") (pinfunction "GND_21") (pintype "passive"))
      (node (ref "U3") (pin "3") (pinfunction "GND_2_3") (pintype "passive"))
      (node (ref "U3") (pin "5") (pinfunction "GND_3_5") (pintype "passive"))
      (node (ref "U4") (pin "8") (pinfunction "GND_8") (pintype "bidirectional"))
      (node (ref "U5") (pin "8") (pinfunction "GND_8") (pintype "bidirectional"))
      (node (ref "U6") (pin "1") (pinfunction "GND_1") (pintype "passive"))
      (node (ref "U7") (pin "1") (pinfunction "GND_1") (pintype "passive"))
      (node (ref "U8") (pin "2") (pinfunction "GND_2") (pintype "bidirectional"))
    )
    (net (code "54") (name "GREEN_0") (class "Default")
      (node (ref "IC2") (pin "41") (pinfunction "IO41_41") (pintype "bidirectional"))
      (node (ref "U$4") (pin "P$13") (pinfunction "P$13_P$13") (pintype "bidirectional"))
    )
    (net (code "55") (name "GREEN_1") (class "Default")
      (node (ref "IC2") (pin "42") (pinfunction "IO42_42") (pintype "bidirectional"))
      (node (ref "U$4") (pin "P$14") (pinfunction "P$14_P$14") (pintype "bidirectional"))
    )
    (net (code "56") (name "GREEN_2") (class "Default")
      (node (ref "IC2") (pin "43") (pinfunction "IO43_43") (pintype "bidirectional"))
      (node (ref "U$4") (pin "P$15") (pinfunction "P$15_P$15") (pintype "bidirectional"))
    )
    (net (code "57") (name "GREEN_3") (class "Default")
      (node (ref "IC2") (pin "44") (pinfunction "IO44_44") (pintype "bidirectional"))
      (node (ref "U$4") (pin "P$16") (pinfunction "P$16_P$16") (pintype "bidirectional"))
    )
    (net (code "58") (name "GREEN_4") (class "Default")
      (node (ref "IC2") (pin "45") (pinfunction "IO45_45") (pintype "bidirectional"))
      (node (ref "U$4") (pin "P$17") (pinfunction "P$17_P$17") (pintype "bidirectional"))
    )
    (net (code "59") (name "GREEN_5") (class "Default")
      (node (ref "IC2") (pin "47") (pinfunction "IO47_47") (pintype "bidirectional"))
      (node (ref "U$4") (pin "P$18") (pinfunction "P$18_P$18") (pintype "bidirectional"))
    )
    (net (code "60") (name "GREEN_6") (class "Default")
      (node (ref "IC2") (pin "48") (pinfunction "IO48_48") (pintype "bidirectional"))
      (node (ref "U$4") (pin "P$19") (pinfunction "P$19_P$19") (pintype "bidirectional"))
    )
    (net (code "61") (name "GREEN_7") (class "Default")
      (node (ref "IC2") (pin "51") (pinfunction "IO51_51") (pintype "bidirectional"))
      (node (ref "U$4") (pin "P$20") (pinfunction "P$20_P$20") (pintype "bidirectional"))
    )
    (net (code "62") (name "LED1") (class "Default")
      (node (ref "IC2") (pin "129") (pinfunction "IO129_129") (pintype "bidirectional"))
      (node (ref "LED1") (pin "C") (pinfunction "C_C") (pintype "passive"))
    )
    (net (code "63") (name "LED2") (class "Default")
      (node (ref "IC2") (pin "132") (pinfunction "IO132_132") (pintype "bidirectional"))
      (node (ref "LED2") (pin "C") (pinfunction "C_C") (pintype "passive"))
    )
    (net (code "64") (name "MISO") (class "Default")
      (node (ref "JP1") (pin "1") (pinfunction "1_1") (pintype "passive"))
      (node (ref "U$2") (pin "15") (pinfunction "SO_15") (pintype "output"))
      (node (ref "U3") (pin "16") (pinfunction "PB4_16") (pintype "bidirectional"))
    )
    (net (code "65") (name "MOSI") (class "Default")
      (node (ref "JP1") (pin "4") (pinfunction "4_4") (pintype "passive"))
      (node (ref "U$2") (pin "14") (pinfunction "SI_14") (pintype "input"))
      (node (ref "U3") (pin "15") (pinfunction "PB3_15") (pintype "bidirectional"))
    )
    (net (code "66") (name "NCE") (class "Default")
      (node (ref "AS1") (pin "6") (pinfunction "6_6") (pintype "passive"))
      (node (ref "IC2") (pin "16") (pinfunction "NCE_16") (pintype "input"))
      (node (ref "R30") (pin "1") (pinfunction "1_1") (pintype "passive"))
    )
    (net (code "67") (name "NCONFIG") (class "Default")
      (node (ref "AS1") (pin "5") (pinfunction "5_5") (pintype "passive"))
      (node (ref "IC2") (pin "20") (pinfunction "NCONFIG_20") (pintype "input"))
      (node (ref "R31") (pin "1") (pinfunction "1_1") (pintype "passive"))
    )
    (net (code "68") (name "NCSO") (class "Default")
      (node (ref "AS1") (pin "8") (pinfunction "8_8") (pintype "passive"))
      (node (ref "IC2") (pin "2") (pinfunction "IO2_2") (pintype "output"))
      (node (ref "U2") (pin "1") (pinfunction "NCS_1") (pintype "input"))
    )
    (net (code "69") (name "NOT_CONNECTED") (class "Default")
      (node (ref "U$4") (pin "P$35") (pinfunction "P$35_P$35") (pintype "bidirectional"))
    )
    (net (code "70") (name "Net-(C8-Pad1)") (class "Default")
      (node (ref "C8") (pin "1") (pinfunction "1_1") (pintype "passive"))
      (node (ref "R8") (pin "1") (pinfunction "1_1") (pintype "passive"))
    )
    (net (code "71") (name "Net-(C9-Pad1)") (class "Default")
      (node (ref "C9") (pin "1") (pinfunction "1_1") (pintype "passive"))
      (node (ref "R9") (pin "1") (pinfunction "1_1") (pintype "passive"))
    )
    (net (code "72") (name "Net-(IC2-NSTATUS)") (class "Default")
      (node (ref "IC2") (pin "82") (pinfunction "NSTATUS_82") (pintype "input"))
      (node (ref "R29") (pin "1") (pinfunction "1_1") (pintype "passive"))
    )
    (net (code "73") (name "Net-(L1-2)") (class "Default")
      (node (ref "D2") (pin "A") (pinfunction "A_A") (pintype "passive"))
      (node (ref "L1") (pin "P$2") (pinfunction "2_P$2") (pintype "passive"))
      (node (ref "U8") (pin "1") (pinfunction "SW_1") (pintype "bidirectional"))
    )
    (net (code "74") (name "Net-(L5-1)") (class "Default")
      (node (ref "FUSE3") (pin "P$1") (pinfunction "1_P$1") (pintype "passive"))
      (node (ref "FUSE3") (pin "P$4") (pinfunction "1_P$4") (pintype "passive"))
      (node (ref "L5") (pin "P$1") (pinfunction "1_P$1") (pintype "passive"))
    )
    (net (code "75") (name "Net-(LED1-PadA)") (class "Default")
      (node (ref "LED1") (pin "A") (pinfunction "A_A") (pintype "passive"))
      (node (ref "R4") (pin "1") (pinfunction "1_1") (pintype "passive"))
    )
    (net (code "76") (name "Net-(LED2-PadA)") (class "Default")
      (node (ref "LED2") (pin "A") (pinfunction "A_A") (pintype "passive"))
      (node (ref "R5") (pin "1") (pinfunction "1_1") (pintype "passive"))
    )
    (net (code "77") (name "Net-(LED3-PadA)") (class "Default")
      (node (ref "LED3") (pin "A") (pinfunction "A_A") (pintype "passive"))
      (node (ref "R6") (pin "1") (pinfunction "1_1") (pintype "passive"))
    )
    (net (code "78") (name "Net-(U$3-RS)") (class "Default")
      (node (ref "R10") (pin "2") (pinfunction "2_2") (pintype "passive"))
      (node (ref "U$3") (pin "8") (pinfunction "RS_8") (pintype "input"))
    )
    (net (code "79") (name "PWR_IN_12") (class "Default")
      (node (ref "FUSE3") (pin "P$2") (pinfunction "2_P$2") (pintype "passive"))
      (node (ref "FUSE3") (pin "P$3") (pinfunction "2_P$3") (pintype "passive"))
      (node (ref "U$1") (pin "4") (pinfunction "7_4") (pintype "passive"))
    )
    (net (code "80") (name "PWR_IN_24") (class "Default")
      (node (ref "U$1") (pin "2") (pinfunction "6_2") (pintype "passive"))
    )
    (net (code "81") (name "RED_0") (class "Default")
      (node (ref "IC2") (pin "25") (pinfunction "IO25_25") (pintype "bidirectional"))
      (node (ref "U$4") (pin "P$5") (pinfunction "P$5_P$5") (pintype "bidirectional"))
    )
    (net (code "82") (name "RED_1") (class "Default")
      (node (ref "IC2") (pin "26") (pinfunction "IO26_26") (pintype "bidirectional"))
      (node (ref "U$4") (pin "P$6") (pinfunction "P$6_P$6") (pintype "bidirectional"))
    )
    (net (code "83") (name "RED_2") (class "Default")
      (node (ref "IC2") (pin "27") (pinfunction "IO27_27") (pintype "bidirectional"))
      (node (ref "U$4") (pin "P$7") (pinfunction "P$7_P$7") (pintype "bidirectional"))
    )
    (net (code "84") (name "RED_3") (class "Default")
      (node (ref "IC2") (pin "28") (pinfunction "IO28_28") (pintype "bidirectional"))
      (node (ref "U$4") (pin "P$8") (pinfunction "P$8_P$8") (pintype "bidirectional"))
    )
    (net (code "85") (name "RED_4") (class "Default")
      (node (ref "IC2") (pin "30") (pinfunction "IO30_30") (pintype "bidirectional"))
      (node (ref "U$4") (pin "P$9") (pinfunction "P$9_P$9") (pintype "bidirectional"))
    )
    (net (code "86") (name "RED_5") (class "Default")
      (node (ref "IC2") (pin "31") (pinfunction "IO31_31") (pintype "bidirectional"))
      (node (ref "U$4") (pin "P$10") (pinfunction "P$10_P$10") (pintype "bidirectional"))
    )
    (net (code "87") (name "RED_6") (class "Default")
      (node (ref "IC2") (pin "32") (pinfunction "IO32_32") (pintype "bidirectional"))
      (node (ref "U$4") (pin "P$11") (pinfunction "P$11_P$11") (pintype "bidirectional"))
    )
    (net (code "88") (name "RED_7") (class "Default")
      (node (ref "IC2") (pin "40") (pinfunction "IO40_40") (pintype "bidirectional"))
      (node (ref "U$4") (pin "P$12") (pinfunction "P$12_P$12") (pintype "bidirectional"))
    )
    (net (code "89") (name "RESET") (class "Default")
      (node (ref "JP1") (pin "5") (pinfunction "5_5") (pintype "passive"))
      (node (ref "R7") (pin "1") (pinfunction "1_1") (pintype "passive"))
      (node (ref "U$2") (pin "17") (pinfunction "~{RESET}_17") (pintype "input"))
      (node (ref "U3") (pin "29") (pinfunction "PC6_29") (pintype "bidirectional"))
    )
    (net (code "90") (name "RXCAN") (class "Default")
      (node (ref "U$2") (pin "2") (pinfunction "RXCAN_2") (pintype "input"))
      (node (ref "U$3") (pin "4") (pinfunction "RXD_4") (pintype "output"))
    )
    (net (code "91") (name "RXD") (class "Default")
      (node (ref "U3") (pin "30") (pinfunction "PD0_30") (pintype "bidirectional"))
    )
    (net (code "92") (name "SCK") (class "Default")
      (node (ref "JP1") (pin "3") (pinfunction "3_3") (pintype "passive"))
      (node (ref "U$2") (pin "13") (pinfunction "SCK_13") (pintype "input"))
      (node (ref "U3") (pin "17") (pinfunction "PB5_17") (pintype "bidirectional"))
    )
    (net (code "93") (name "TCK") (class "Default")
      (node (ref "IC2") (pin "12") (pinfunction "TCK_12") (pintype "input"))
      (node (ref "JTAG1") (pin "1") (pinfunction "1_1") (pintype "passive"))
      (node (ref "R27") (pin "2") (pinfunction "2_2") (pintype "passive"))
    )
    (net (code "94") (name "TDI") (class "Default")
      (node (ref "IC2") (pin "13") (pinfunction "TDI_13") (pintype "input"))
      (node (ref "JTAG1") (pin "9") (pinfunction "9_9") (pintype "passive"))
      (node (ref "R28") (pin "2") (pinfunction "2_2") (pintype "passive"))
    )
    (net (code "95") (name "TDO") (class "Default")
      (node (ref "IC2") (pin "10") (pinfunction "TDO_10") (pintype "output"))
      (node (ref "JTAG1") (pin "3") (pinfunction "3_3") (pintype "passive"))
    )
    (net (code "96") (name "TMS") (class "Default")
      (node (ref "IC2") (pin "11") (pinfunction "TMS_11") (pintype "input"))
      (node (ref "JTAG1") (pin "5") (pinfunction "5_5") (pintype "passive"))
      (node (ref "R33") (pin "1") (pinfunction "1_1") (pintype "passive"))
    )
    (net (code "97") (name "TXCAN") (class "Default")
      (node (ref "U$2") (pin "1") (pinfunction "TXCAN_1") (pintype "output"))
      (node (ref "U$3") (pin "1") (pinfunction "TXD_1") (pintype "input"))
    )
    (net (code "98") (name "TXD") (class "Default")
      (node (ref "U3") (pin "31") (pinfunction "PD1_31") (pintype "bidirectional"))
    )
    (net (code "99") (name "VCC") (class "Default")
      (node (ref "C1") (pin "1") (pinfunction "1_1") (pintype "passive"))
      (node (ref "IC2") (pin "107") (pinfunction "VCC_107") (pintype "power_in"))
      (node (ref "IC2") (pin "109") (pinfunction "VCC_109") (pintype "power_in"))
      (node (ref "IC2") (pin "124") (pinfunction "VCC_124") (pintype "power_in"))
      (node (ref "IC2") (pin "131") (pinfunction "VCC_131") (pintype "power_in"))
      (node (ref "IC2") (pin "35") (pinfunction "VCC_35") (pintype "power_in"))
      (node (ref "IC2") (pin "37") (pinfunction "VCC_37") (pintype "power_in"))
      (node (ref "IC2") (pin "50") (pinfunction "VCC_50") (pintype "power_in"))
      (node (ref "IC2") (pin "62") (pinfunction "VCC_62") (pintype "power_in"))
      (node (ref "U$5") (pin "2") (pinfunction "VOUT_2") (pintype "output"))
    )
    (net (code "100") (name "XTAL1") (class "Default")
      (node (ref "C3") (pin "2") (pinfunction "2_2") (pintype "passive"))
      (node (ref "Q3") (pin "3") (pinfunction "2_3") (pintype "passive"))
      (node (ref "U3") (pin "7") (pinfunction "PB6_7") (pintype "bidirectional"))
    )
    (net (code "101") (name "XTAL2") (class "Default")
      (node (ref "C4") (pin "1") (pinfunction "1_1") (pintype "passive"))
      (node (ref "Q3") (pin "1") (pinfunction "1_1") (pintype "passive"))
      (node (ref "U3") (pin "8") (pinfunction "PB7_8") (pintype "bidirectional"))
    )
    (net (code "102") (name "unconnected-(IC2-CLK1-Pad18)") (class "Default")
      (node (ref "IC2") (pin "18") (pinfunction "CLK1_18") (pintype "bidirectional"))
    )
    (net (code "103") (name "unconnected-(IC2-CLK2-Pad21)") (class "Default")
      (node (ref "IC2") (pin "21") (pinfunction "CLK2_21") (pintype "bidirectional"))
    )
    (net (code "104") (name "unconnected-(IC2-CLK3-Pad22)") (class "Default")
      (node (ref "IC2") (pin "22") (pinfunction "CLK3_22") (pintype "bidirectional"))
    )
    (net (code "105") (name "unconnected-(IC2-CLK4-Pad91)") (class "Default")
      (node (ref "IC2") (pin "91") (pinfunction "CLK4_91") (pintype "bidirectional"))
    )
    (net (code "106") (name "unconnected-(IC2-CLK5-Pad90)") (class "Default")
      (node (ref "IC2") (pin "90") (pinfunction "CLK5_90") (pintype "bidirectional"))
    )
    (net (code "107") (name "unconnected-(IC2-CLK6-Pad89)") (class "Default")
      (node (ref "IC2") (pin "89") (pinfunction "CLK6_89") (pintype "bidirectional"))
    )
    (net (code "108") (name "unconnected-(IC2-CLK7-Pad88)") (class "Default")
      (node (ref "IC2") (pin "88") (pinfunction "CLK7_88") (pintype "bidirectional"))
    )
    (net (code "109") (name "unconnected-(IC2-IO24-Pad24)") (class "Default")
      (node (ref "IC2") (pin "24") (pinfunction "IO24_24") (pintype "bidirectional"))
    )
    (net (code "110") (name "unconnected-(IC2-IO64-Pad64)") (class "Default")
      (node (ref "IC2") (pin "64") (pinfunction "IO64_64") (pintype "bidirectional"))
    )
    (net (code "111") (name "unconnected-(IC2-IO65-Pad65)") (class "Default")
      (node (ref "IC2") (pin "65") (pinfunction "IO65_65") (pintype "bidirectional"))
    )
    (net (code "112") (name "unconnected-(IC2-IO67-Pad67)") (class "Default")
      (node (ref "IC2") (pin "67") (pinfunction "IO67_67") (pintype "bidirectional"))
    )
    (net (code "113") (name "unconnected-(IC2-IO69-Pad69)") (class "Default")
      (node (ref "IC2") (pin "69") (pinfunction "IO69_69") (pintype "bidirectional"))
    )
    (net (code "114") (name "unconnected-(IC2-IO70-Pad70)") (class "Default")
      (node (ref "IC2") (pin "70") (pinfunction "IO70_70") (pintype "bidirectional"))
    )
    (net (code "115") (name "unconnected-(IC2-IO71-Pad71)") (class "Default")
      (node (ref "IC2") (pin "71") (pinfunction "IO71_71") (pintype "bidirectional"))
    )
    (net (code "116") (name "unconnected-(IC2-IO72-Pad72)") (class "Default")
      (node (ref "IC2") (pin "72") (pinfunction "IO72_72") (pintype "bidirectional"))
    )
    (net (code "117") (name "unconnected-(IC2-IO93-Pad93)") (class "Default")
      (node (ref "IC2") (pin "93") (pinfunction "IO93_93") (pintype "bidirectional"))
    )
    (net (code "118") (name "unconnected-(IC2-IO94-Pad94)") (class "Default")
      (node (ref "IC2") (pin "94") (pinfunction "IO94_94") (pintype "bidirectional"))
    )
    (net (code "119") (name "unconnected-(IC2-IO96-Pad96)") (class "Default")
      (node (ref "IC2") (pin "96") (pinfunction "IO96_96") (pintype "bidirectional"))
    )
    (net (code "120") (name "unconnected-(IC2-IO97-Pad97)") (class "Default")
      (node (ref "IC2") (pin "97") (pinfunction "IO97_97") (pintype "bidirectional"))
    )
    (net (code "121") (name "unconnected-(IC2-IO99-Pad99)") (class "Default")
      (node (ref "IC2") (pin "99") (pinfunction "IO99_99") (pintype "bidirectional"))
    )
    (net (code "122") (name "unconnected-(IC2-IO100-Pad100)") (class "Default")
      (node (ref "IC2") (pin "100") (pinfunction "IO100_100") (pintype "bidirectional"))
    )
    (net (code "123") (name "unconnected-(IC2-IO101-Pad101)") (class "Default")
      (node (ref "IC2") (pin "101") (pinfunction "IO101_101") (pintype "bidirectional"))
    )
    (net (code "124") (name "unconnected-(IC2-IO103-Pad103)") (class "Default")
      (node (ref "IC2") (pin "103") (pinfunction "IO103_103") (pintype "bidirectional"))
    )
    (net (code "125") (name "unconnected-(IC2-IO104-Pad104)") (class "Default")
      (node (ref "IC2") (pin "104") (pinfunction "IO104_104") (pintype "bidirectional"))
    )
    (net (code "126") (name "unconnected-(IC2-IO112-Pad112)") (class "Default")
      (node (ref "IC2") (pin "112") (pinfunction "IO112_112") (pintype "bidirectional"))
    )
    (net (code "127") (name "unconnected-(IC2-IO113-Pad113)") (class "Default")
      (node (ref "IC2") (pin "113") (pinfunction "IO113_113") (pintype "bidirectional"))
    )
    (net (code "128") (name "unconnected-(IC2-IO114-Pad114)") (class "Default")
      (node (ref "IC2") (pin "114") (pinfunction "IO114_114") (pintype "bidirectional"))
    )
    (net (code "129") (name "unconnected-(IC2-IO115-Pad115)") (class "Default")
      (node (ref "IC2") (pin "115") (pinfunction "IO115_115") (pintype "bidirectional"))
    )
    (net (code "130") (name "unconnected-(IC2-IO118-Pad118)") (class "Default")
      (node (ref "IC2") (pin "118") (pinfunction "IO118_118") (pintype "bidirectional"))
    )
    (net (code "131") (name "unconnected-(IC2-IO119-Pad119)") (class "Default")
      (node (ref "IC2") (pin "119") (pinfunction "IO119_119") (pintype "bidirectional"))
    )
    (net (code "132") (name "unconnected-(IC2-IO120-Pad120)") (class "Default")
      (node (ref "IC2") (pin "120") (pinfunction "IO120_120") (pintype "bidirectional"))
    )
    (net (code "133") (name "unconnected-(IC2-IO121-Pad121)") (class "Default")
      (node (ref "IC2") (pin "121") (pinfunction "IO121_121") (pintype "bidirectional"))
    )
    (net (code "134") (name "unconnected-(IC2-IO122-Pad122)") (class "Default")
      (node (ref "IC2") (pin "122") (pinfunction "IO122_122") (pintype "bidirectional"))
    )
    (net (code "135") (name "unconnected-(IC2-IO125-Pad125)") (class "Default")
      (node (ref "IC2") (pin "125") (pinfunction "IO125_125") (pintype "bidirectional"))
    )
    (net (code "136") (name "unconnected-(IC2-IO126-Pad126)") (class "Default")
      (node (ref "IC2") (pin "126") (pinfunction "IO126_126") (pintype "bidirectional"))
    )
    (net (code "137") (name "unconnected-(IC2-IO133-Pad133)") (class "Default")
      (node (ref "IC2") (pin "133") (pinfunction "IO133_133") (pintype "bidirectional"))
    )
    (net (code "138") (name "unconnected-(IC2-IO134-Pad134)") (class "Default")
      (node (ref "IC2") (pin "134") (pinfunction "IO134_134") (pintype "bidirectional"))
    )
    (net (code "139") (name "unconnected-(IC2-IO135-Pad135)") (class "Default")
      (node (ref "IC2") (pin "135") (pinfunction "IO135_135") (pintype "bidirectional"))
    )
    (net (code "140") (name "unconnected-(IC2-IO136-Pad136)") (class "Default")
      (node (ref "IC2") (pin "136") (pinfunction "IO136_136") (pintype "bidirectional"))
    )
    (net (code "141") (name "unconnected-(IC2-IO137-Pad137)") (class "Default")
      (node (ref "IC2") (pin "137") (pinfunction "IO137_137") (pintype "bidirectional"))
    )
    (net (code "142") (name "unconnected-(IC2-IO139-Pad139)") (class "Default")
      (node (ref "IC2") (pin "139") (pinfunction "IO139_139") (pintype "bidirectional"))
    )
    (net (code "143") (name "unconnected-(IC2-IO141-Pad141)") (class "Default")
      (node (ref "IC2") (pin "141") (pinfunction "IO141_141") (pintype "bidirectional"))
    )
    (net (code "144") (name "unconnected-(IC2-IO142-Pad142)") (class "Default")
      (node (ref "IC2") (pin "142") (pinfunction "IO142_142") (pintype "bidirectional"))
    )
    (net (code "145") (name "unconnected-(IC2-IO143-Pad143)") (class "Default")
      (node (ref "IC2") (pin "143") (pinfunction "IO143_143") (pintype "bidirectional"))
    )
    (net (code "146") (name "unconnected-(IC2-IO144-Pad144)") (class "Default")
      (node (ref "IC2") (pin "144") (pinfunction "IO144_144") (pintype "bidirectional"))
    )
    (net (code "147") (name "unconnected-(JTAG1-Pad6)") (class "Default")
      (node (ref "JTAG1") (pin "6") (pinfunction "6_6") (pintype "passive"))
    )
    (net (code "148") (name "unconnected-(JTAG1-Pad7)") (class "Default")
      (node (ref "JTAG1") (pin "7") (pinfunction "7_7") (pintype "passive"))
    )
    (net (code "149") (name "unconnected-(JTAG1-Pad8)") (class "Default")
      (node (ref "JTAG1") (pin "8") (pinfunction "8_8") (pintype "passive"))
    )
    (net (code "150") (name "unconnected-(QG2-E{slash}D-Pad1)") (class "Default")
      (node (ref "QG2") (pin "1") (pinfunction "E/D_1") (pintype "input"))
    )
    (net (code "151") (name "unconnected-(U$1-1-Pad6)") (class "Default")
      (node (ref "U$1") (pin "6") (pinfunction "1_6") (pintype "passive"))
    )
    (net (code "152") (name "unconnected-(U$1-2-Pad8)") (class "Default")
      (node (ref "U$1") (pin "8") (pinfunction "2_8") (pintype "passive"))
    )
    (net (code "153") (name "unconnected-(U$1-3-Pad7)") (class "Default")
      (node (ref "U$1") (pin "7") (pinfunction "3_7") (pintype "passive"))
    )
    (net (code "154") (name "unconnected-(U$2-CLKOUT{slash}SOF-Pad3)") (class "Default")
      (node (ref "U$2") (pin "3") (pinfunction "CLKOUT/SOF_3") (pintype "output"))
    )
    (net (code "155") (name "unconnected-(U$2-~{RX0BF}-Pad11)") (class "Default")
      (node (ref "U$2") (pin "11") (pinfunction "~{RX0BF}_11") (pintype "output"))
    )
    (net (code "156") (name "unconnected-(U$2-~{RX1BF}-Pad10)") (class "Default")
      (node (ref "U$2") (pin "10") (pinfunction "~{RX1BF}_10") (pintype "output"))
    )
    (net (code "157") (name "unconnected-(U$2-~{TX0RTS}-Pad4)") (class "Default")
      (node (ref "U$2") (pin "4") (pinfunction "~{TX0RTS}_4") (pintype "input"))
    )
    (net (code "158") (name "unconnected-(U$2-~{TX1RTS}-Pad5)") (class "Default")
      (node (ref "U$2") (pin "5") (pinfunction "~{TX1RTS}_5") (pintype "input"))
    )
    (net (code "159") (name "unconnected-(U$2-~{TX2RTS}-Pad6)") (class "Default")
      (node (ref "U$2") (pin "6") (pinfunction "~{TX2RTS}_6") (pintype "input"))
    )
    (net (code "160") (name "unconnected-(U$3-VREF-Pad5)") (class "Default")
      (node (ref "U$3") (pin "5") (pinfunction "VREF_5") (pintype "output"))
    )
    (net (code "161") (name "unconnected-(U3-ADC6-Pad19)") (class "Default")
      (node (ref "U3") (pin "19") (pinfunction "ADC6_19") (pintype "input"))
    )
    (net (code "162") (name "unconnected-(U3-ADC7-Pad22)") (class "Default")
      (node (ref "U3") (pin "22") (pinfunction "ADC7_22") (pintype "input"))
    )
    (net (code "163") (name "unconnected-(U3-AREF-Pad20)") (class "Default")
      (node (ref "U3") (pin "20") (pinfunction "AREF_20") (pintype "input"))
    )
    (net (code "164") (name "unconnected-(U3-PB0-Pad12)") (class "Default")
      (node (ref "U3") (pin "12") (pinfunction "PB0_12") (pintype "bidirectional"))
    )
    (net (code "165") (name "unconnected-(U3-PB2-Pad14)") (class "Default")
      (node (ref "U3") (pin "14") (pinfunction "PB2_14") (pintype "bidirectional"))
    )
    (net (code "166") (name "unconnected-(U5-5A-Pad11)") (class "Default")
      (node (ref "U5") (pin "11") (pinfunction "5A_11") (pintype "bidirectional"))
    )
    (net (code "167") (name "unconnected-(U5-5Y-Pad12)") (class "Default")
      (node (ref "U5") (pin "12") (pinfunction "5Y_12") (pintype "bidirectional"))
    )
    (net (code "168") (name "unconnected-(U5-6A-Pad14)") (class "Default")
      (node (ref "U5") (pin "14") (pinfunction "6A_14") (pintype "bidirectional"))
    )
    (net (code "169") (name "unconnected-(U5-6Y-Pad15)") (class "Default")
      (node (ref "U5") (pin "15") (pinfunction "6Y_15") (pintype "bidirectional"))
    )
    (net (code "170") (name "unconnected-(U6-N{slash}C-Pad4)") (class "Default")
      (node (ref "U6") (pin "4") (pinfunction "N/C_4") (pintype "no_connect"))
    )
    (net (code "171") (name "unconnected-(U6-N{slash}C_2-Pad5)") (class "Default")
      (node (ref "U6") (pin "5") (pinfunction "N/C_2_5") (pintype "no_connect"))
    )
    (net (code "172") (name "unconnected-(U7-N{slash}C-Pad4)") (class "Default")
      (node (ref "U7") (pin "4") (pinfunction "N/C_4") (pintype "no_connect"))
    )
    (net (code "173") (name "unconnected-(U7-N{slash}C_2-Pad5)") (class "Default")
      (node (ref "U7") (pin "5") (pinfunction "N/C_2_5") (pintype "no_connect"))
    )
    (net (code "174") (name "~{CS_CAN}") (class "Default")
      (node (ref "U$2") (pin "16") (pinfunction "~{CS}_16") (pintype "input"))
      (node (ref "U3") (pin "28") (pinfunction "PC5_28") (pintype "bidirectional"))
    )
    (net (code "175") (name "~{INT_CAN}") (class "Default")
      (node (ref "U$2") (pin "12") (pinfunction "~{INT}_12") (pintype "output"))
      (node (ref "U3") (pin "32") (pinfunction "PD2_32") (pintype "bidirectional"))
    )
  )
)
